# 04B-345.net
KiCad netlist of a schematic drawn in EAGLE
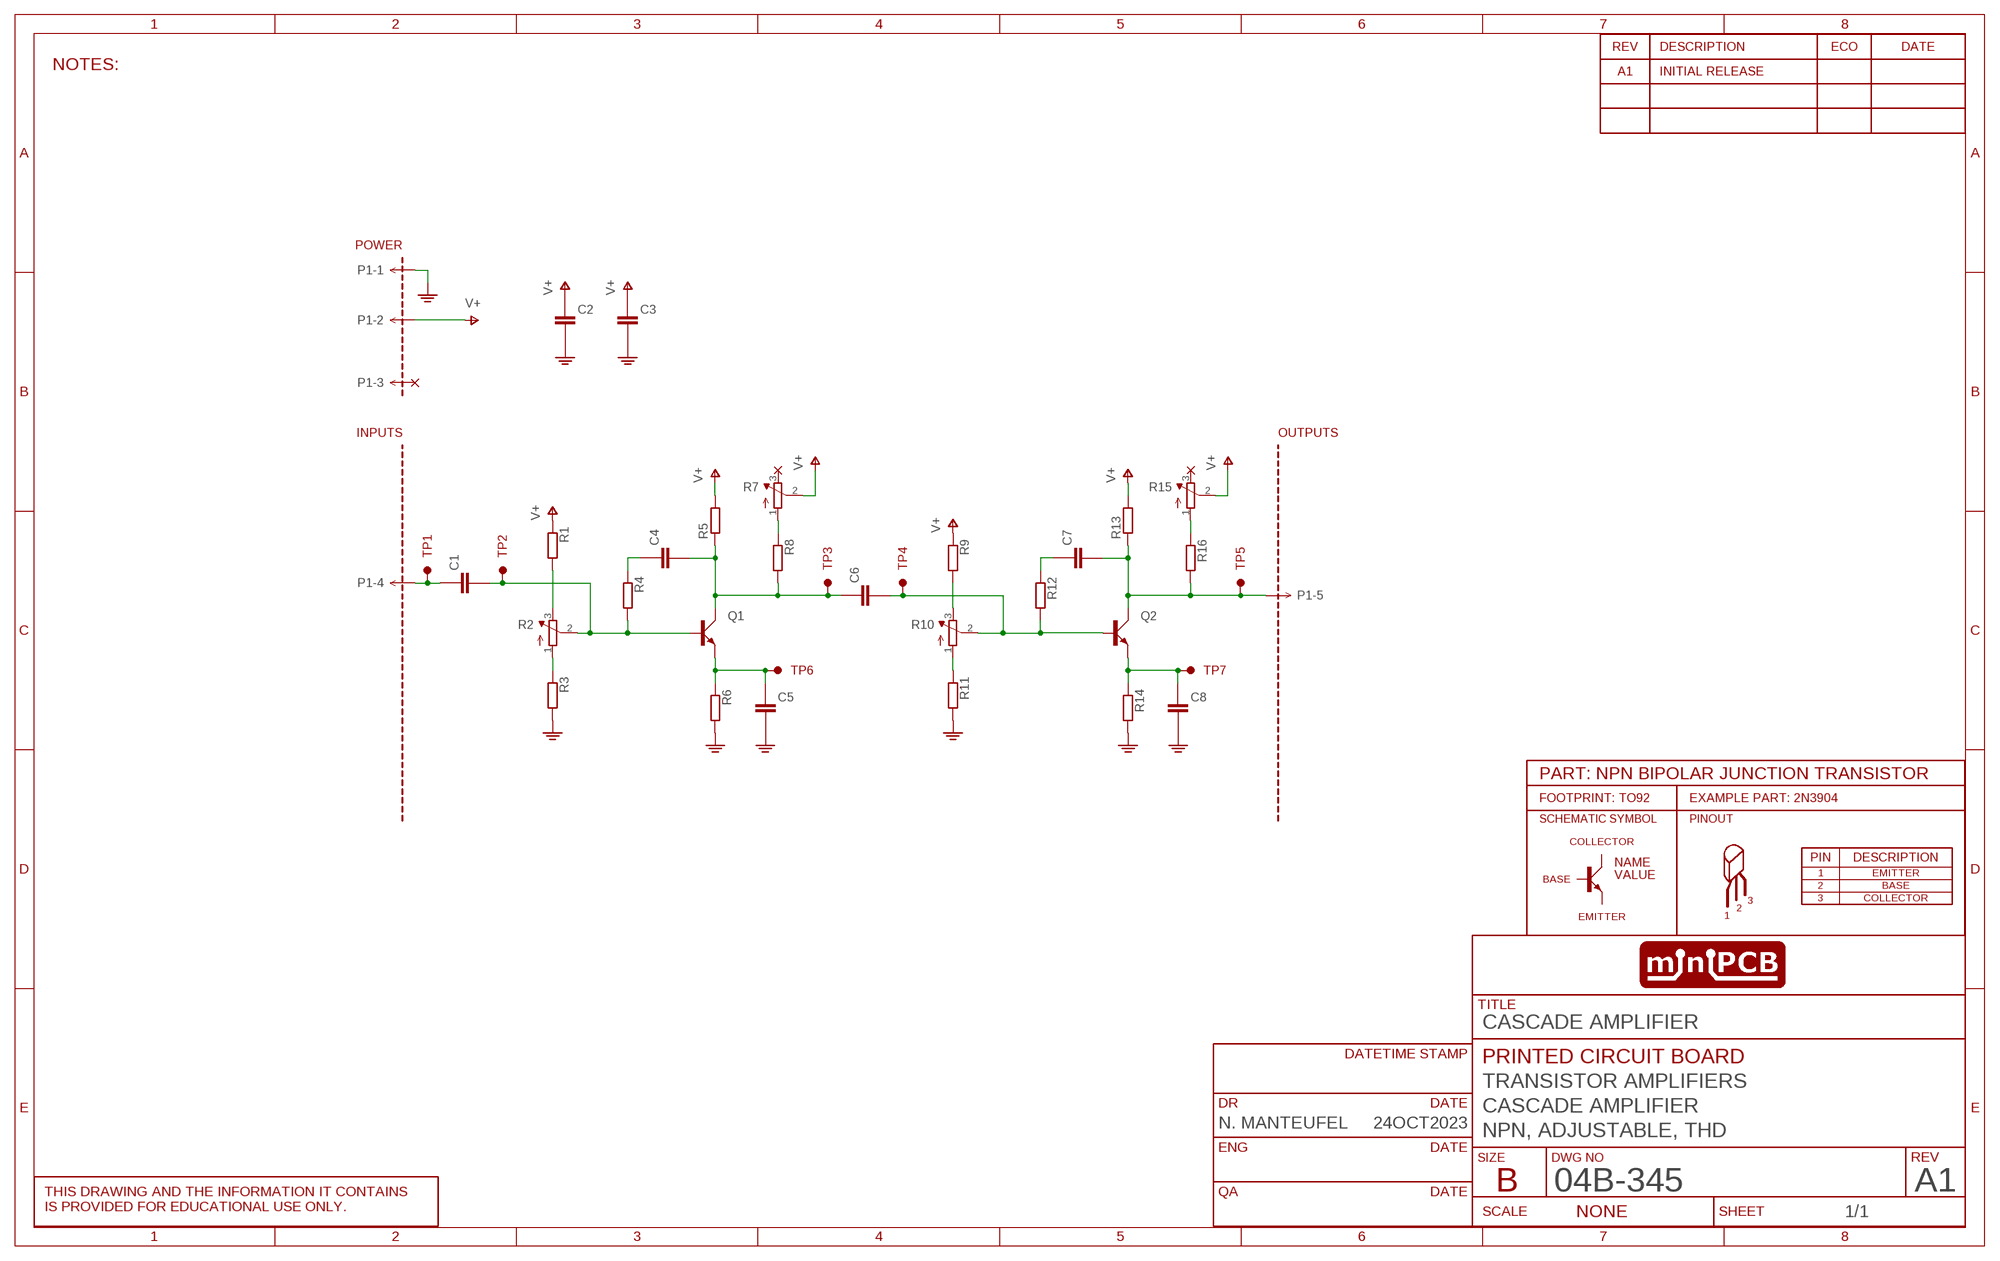
[diagram p0: schematic, sheet 1]

(export (version "E")
  (design (tool "Eeschema 10.0.6"))
  (components
    (comp (ref "C1")
      (value "CAPACITORTHD")
      (footprint "eagle-import:C050-024X044")
      (libsource (lib "eagle-import") (part "CAPACITORTHD"))
    )
    (comp (ref "C2")
      (value "CAPACITORTHD")
      (footprint "eagle-import:C050-024X044")
      (libsource (lib "eagle-import") (part "CAPACITORTHD"))
    )
    (comp (ref "C3")
      (value "CAPACITOR_10")
      (footprint "eagle-import:C5MM")
      (libsource (lib "eagle-import") (part "CAPACITOR_10"))
    )
    (comp (ref "C4")
      (value "CAPACITORTHD")
      (footprint "eagle-import:C050-024X044")
      (libsource (lib "eagle-import") (part "CAPACITORTHD"))
    )
    (comp (ref "C5")
      (value "CAPACITOR_10")
      (footprint "eagle-import:C5MM")
      (libsource (lib "eagle-import") (part "CAPACITOR_10"))
    )
    (comp (ref "C6")
      (value "CAPACITORTHD")
      (footprint "eagle-import:C050-024X044")
      (libsource (lib "eagle-import") (part "CAPACITORTHD"))
    )
    (comp (ref "C7")
      (value "CAPACITORTHD")
      (footprint "eagle-import:C050-024X044")
      (libsource (lib "eagle-import") (part "CAPACITORTHD"))
    )
    (comp (ref "C8")
      (value "CAPACITOR_10")
      (footprint "eagle-import:C5MM")
      (libsource (lib "eagle-import") (part "CAPACITOR_10"))
    )
    (comp (ref "P1")
      (value "MINIPCB_5P5P")
      (footprint "eagle-import:PINS_1X5")
      (libsource (lib "eagle-import") (part "MINIPCB_5P5P"))
    )
    (comp (ref "PCB1")
      (value "MINIPCB_0P50X75")
      (footprint "eagle-import:MINIPCB_0P_50X75")
      (libsource (lib "eagle-import") (part "MINIPCB_0P50X75"))
    )
    (comp (ref "Q1")
      (value "BJT_NPNEBC")
      (footprint "eagle-import:TO92-EBC-OVAL")
      (libsource (lib "eagle-import") (part "BJT_NPNEBC"))
    )
    (comp (ref "Q2")
      (value "BJT_NPNEBC")
      (footprint "eagle-import:TO92-EBC-OVAL")
      (libsource (lib "eagle-import") (part "BJT_NPNEBC"))
    )
    (comp (ref "R1")
      (value "RESISTORTHD")
      (footprint "eagle-import:0204_10")
      (libsource (lib "eagle-import") (part "RESISTORTHD"))
    )
    (comp (ref "R2")
      (value "TRIMPOT0.100THD")
      (footprint "eagle-import:TRIM_0100")
      (libsource (lib "eagle-import") (part "TRIMPOT0.100THD"))
    )
    (comp (ref "R3")
      (value "RESISTORTHD")
      (footprint "eagle-import:0204_10")
      (libsource (lib "eagle-import") (part "RESISTORTHD"))
    )
    (comp (ref "R4")
      (value "RESISTORTHD")
      (footprint "eagle-import:0204_10")
      (libsource (lib "eagle-import") (part "RESISTORTHD"))
    )
    (comp (ref "R5")
      (value "RESISTORTHD")
      (footprint "eagle-import:0204_10")
      (libsource (lib "eagle-import") (part "RESISTORTHD"))
    )
    (comp (ref "R6")
      (value "RESISTORTHD")
      (footprint "eagle-import:0204_10")
      (libsource (lib "eagle-import") (part "RESISTORTHD"))
    )
    (comp (ref "R7")
      (value "TRIMPOT0.100THD")
      (footprint "eagle-import:TRIM_0100")
      (libsource (lib "eagle-import") (part "TRIMPOT0.100THD"))
    )
    (comp (ref "R8")
      (value "RESISTORTHD")
      (footprint "eagle-import:0204_10")
      (libsource (lib "eagle-import") (part "RESISTORTHD"))
    )
    (comp (ref "R9")
      (value "RESISTORTHD")
      (footprint "eagle-import:0204_10")
      (libsource (lib "eagle-import") (part "RESISTORTHD"))
    )
    (comp (ref "R10")
      (value "TRIMPOT0.100THD")
      (footprint "eagle-import:TRIM_0100")
      (libsource (lib "eagle-import") (part "TRIMPOT0.100THD"))
    )
    (comp (ref "R11")
      (value "RESISTORTHD")
      (footprint "eagle-import:0204_10")
      (libsource (lib "eagle-import") (part "RESISTORTHD"))
    )
    (comp (ref "R12")
      (value "RESISTORTHD")
      (footprint "eagle-import:0204_10")
      (libsource (lib "eagle-import") (part "RESISTORTHD"))
    )
    (comp (ref "R13")
      (value "RESISTORTHD")
      (footprint "eagle-import:0204_10")
      (libsource (lib "eagle-import") (part "RESISTORTHD"))
    )
    (comp (ref "R14")
      (value "RESISTORTHD")
      (footprint "eagle-import:0204_10")
      (libsource (lib "eagle-import") (part "RESISTORTHD"))
    )
    (comp (ref "R15")
      (value "TRIMPOT0.100THD")
      (footprint "eagle-import:TRIM_0100")
      (libsource (lib "eagle-import") (part "TRIMPOT0.100THD"))
    )
    (comp (ref "R16")
      (value "RESISTORTHD")
      (footprint "eagle-import:0204_10")
      (libsource (lib "eagle-import") (part "RESISTORTHD"))
    )
    (comp (ref "TP1")
      (value "TESTPOINTKE5000-SMTEXT")
      (footprint "eagle-import:PINS_1_TESTPOINT_KE5000_NOTEXT")
      (libsource (lib "eagle-import") (part "TESTPOINTKE5000-SMTEXT"))
    )
    (comp (ref "TP2")
      (value "TESTPOINTKE5000-SMTEXT")
      (footprint "eagle-import:PINS_1_TESTPOINT_KE5000_NOTEXT")
      (libsource (lib "eagle-import") (part "TESTPOINTKE5000-SMTEXT"))
    )
    (comp (ref "TP3")
      (value "TESTPOINTKE5000-SMTEXT")
      (footprint "eagle-import:PINS_1_TESTPOINT_KE5000_NOTEXT")
      (libsource (lib "eagle-import") (part "TESTPOINTKE5000-SMTEXT"))
    )
    (comp (ref "TP4")
      (value "TESTPOINTKE5000-SMTEXT")
      (footprint "eagle-import:PINS_1_TESTPOINT_KE5000_NOTEXT")
      (libsource (lib "eagle-import") (part "TESTPOINTKE5000-SMTEXT"))
    )
    (comp (ref "TP5")
      (value "TESTPOINTKE5000-SMTEXT")
      (footprint "eagle-import:PINS_1_TESTPOINT_KE5000_NOTEXT")
      (libsource (lib "eagle-import") (part "TESTPOINTKE5000-SMTEXT"))
    )
    (comp (ref "TP6")
      (value "TESTPOINTKE5000-SMTEXT")
      (footprint "eagle-import:PINS_1_TESTPOINT_KE5000_NOTEXT")
      (libsource (lib "eagle-import") (part "TESTPOINTKE5000-SMTEXT"))
    )
    (comp (ref "TP7")
      (value "TESTPOINTKE5000-SMTEXT")
      (footprint "eagle-import:PINS_1_TESTPOINT_KE5000_NOTEXT")
      (libsource (lib "eagle-import") (part "TESTPOINTKE5000-SMTEXT"))
    )
  )
  (nets
    (net (code "1") (name "GND") (class "Default")
      (node (ref "C2") (pin "2") (pinfunction "-_2") (pintype "passive"))
      (node (ref "C3") (pin "-") (pinfunction "-_-") (pintype "passive"))
      (node (ref "C5") (pin "-") (pinfunction "-_-") (pintype "passive"))
      (node (ref "C8") (pin "-") (pinfunction "-_-") (pintype "passive"))
      (node (ref "P1") (pin "1") (pinfunction "1_1") (pintype "bidirectional"))
      (node (ref "R11") (pin "2") (pinfunction "2_2") (pintype "passive"))
      (node (ref "R14") (pin "2") (pinfunction "2_2") (pintype "passive"))
      (node (ref "R3") (pin "2") (pinfunction "2_2") (pintype "passive"))
      (node (ref "R6") (pin "2") (pinfunction "2_2") (pintype "passive"))
    )
    (net (code "2") (name "Net-(C1-+)") (class "Default")
      (node (ref "C1") (pin "1") (pinfunction "+_1") (pintype "passive"))
      (node (ref "P1") (pin "4") (pinfunction "1_4") (pintype "bidirectional"))
      (node (ref "TP1") (pin "1") (pinfunction "1_1") (pintype "bidirectional"))
    )
    (net (code "3") (name "Net-(C1--)") (class "Default")
      (node (ref "C1") (pin "2") (pinfunction "-_2") (pintype "passive"))
      (node (ref "Q1") (pin "B") (pinfunction "B_B") (pintype "passive"))
      (node (ref "R2") (pin "2") (pinfunction "S_2") (pintype "passive"))
      (node (ref "R4") (pin "2") (pinfunction "2_2") (pintype "passive"))
      (node (ref "TP2") (pin "1") (pinfunction "1_1") (pintype "bidirectional"))
    )
    (net (code "4") (name "Net-(C4-+)") (class "Default")
      (node (ref "C4") (pin "1") (pinfunction "+_1") (pintype "passive"))
      (node (ref "R4") (pin "1") (pinfunction "1_1") (pintype "passive"))
    )
    (net (code "5") (name "Net-(C4--)") (class "Default")
      (node (ref "C4") (pin "2") (pinfunction "-_2") (pintype "passive"))
      (node (ref "C6") (pin "1") (pinfunction "+_1") (pintype "passive"))
      (node (ref "Q1") (pin "C") (pinfunction "C_C") (pintype "passive"))
      (node (ref "R5") (pin "1") (pinfunction "1_1") (pintype "passive"))
      (node (ref "R8") (pin "2") (pinfunction "2_2") (pintype "passive"))
      (node (ref "TP3") (pin "1") (pinfunction "1_1") (pintype "bidirectional"))
    )
    (net (code "6") (name "Net-(C5-Pad+)") (class "Default")
      (node (ref "C5") (pin "+") (pinfunction "+_+") (pintype "passive"))
      (node (ref "Q1") (pin "E") (pinfunction "E_E") (pintype "passive"))
      (node (ref "R6") (pin "1") (pinfunction "1_1") (pintype "passive"))
      (node (ref "TP6") (pin "1") (pinfunction "1_1") (pintype "bidirectional"))
    )
    (net (code "7") (name "Net-(C6--)") (class "Default")
      (node (ref "C6") (pin "2") (pinfunction "-_2") (pintype "passive"))
      (node (ref "Q2") (pin "B") (pinfunction "B_B") (pintype "passive"))
      (node (ref "R10") (pin "2") (pinfunction "S_2") (pintype "passive"))
      (node (ref "R12") (pin "2") (pinfunction "2_2") (pintype "passive"))
      (node (ref "TP4") (pin "1") (pinfunction "1_1") (pintype "bidirectional"))
    )
    (net (code "8") (name "Net-(C7-+)") (class "Default")
      (node (ref "C7") (pin "1") (pinfunction "+_1") (pintype "passive"))
      (node (ref "R12") (pin "1") (pinfunction "1_1") (pintype "passive"))
    )
    (net (code "9") (name "Net-(C7--)") (class "Default")
      (node (ref "C7") (pin "2") (pinfunction "-_2") (pintype "passive"))
      (node (ref "P1") (pin "5") (pinfunction "1_5") (pintype "bidirectional"))
      (node (ref "Q2") (pin "C") (pinfunction "C_C") (pintype "passive"))
      (node (ref "R13") (pin "1") (pinfunction "1_1") (pintype "passive"))
      (node (ref "R16") (pin "2") (pinfunction "2_2") (pintype "passive"))
      (node (ref "TP5") (pin "1") (pinfunction "1_1") (pintype "bidirectional"))
    )
    (net (code "10") (name "Net-(C8-Pad+)") (class "Default")
      (node (ref "C8") (pin "+") (pinfunction "+_+") (pintype "passive"))
      (node (ref "Q2") (pin "E") (pinfunction "E_E") (pintype "passive"))
      (node (ref "R14") (pin "1") (pinfunction "1_1") (pintype "passive"))
      (node (ref "TP7") (pin "1") (pinfunction "1_1") (pintype "bidirectional"))
    )
    (net (code "11") (name "Net-(R2-A)") (class "Default")
      (node (ref "R2") (pin "1") (pinfunction "A_1") (pintype "passive"))
      (node (ref "R3") (pin "1") (pinfunction "1_1") (pintype "passive"))
    )
    (net (code "12") (name "Net-(R2-E)") (class "Default")
      (node (ref "R1") (pin "2") (pinfunction "2_2") (pintype "passive"))
      (node (ref "R2") (pin "3") (pinfunction "E_3") (pintype "passive"))
    )
    (net (code "13") (name "Net-(R7-A)") (class "Default")
      (node (ref "R7") (pin "1") (pinfunction "A_1") (pintype "passive"))
      (node (ref "R8") (pin "1") (pinfunction "1_1") (pintype "passive"))
    )
    (net (code "14") (name "Net-(R10-A)") (class "Default")
      (node (ref "R10") (pin "1") (pinfunction "A_1") (pintype "passive"))
      (node (ref "R11") (pin "1") (pinfunction "1_1") (pintype "passive"))
    )
    (net (code "15") (name "Net-(R10-E)") (class "Default")
      (node (ref "R10") (pin "3") (pinfunction "E_3") (pintype "passive"))
      (node (ref "R9") (pin "2") (pinfunction "2_2") (pintype "passive"))
    )
    (net (code "16") (name "Net-(R15-A)") (class "Default")
      (node (ref "R15") (pin "1") (pinfunction "A_1") (pintype "passive"))
      (node (ref "R16") (pin "1") (pinfunction "1_1") (pintype "passive"))
    )
    (net (code "17") (name "V+") (class "Default")
      (node (ref "C2") (pin "1") (pinfunction "+_1") (pintype "passive"))
      (node (ref "C3") (pin "+") (pinfunction "+_+") (pintype "passive"))
      (node (ref "P1") (pin "2") (pinfunction "1_2") (pintype "bidirectional"))
      (node (ref "R1") (pin "1") (pinfunction "1_1") (pintype "passive"))
      (node (ref "R13") (pin "2") (pinfunction "2_2") (pintype "passive"))
      (node (ref "R15") (pin "2") (pinfunction "S_2") (pintype "passive"))
      (node (ref "R5") (pin "2") (pinfunction "2_2") (pintype "passive"))
      (node (ref "R7") (pin "2") (pinfunction "S_2") (pintype "passive"))
      (node (ref "R9") (pin "1") (pinfunction "1_1") (pintype "passive"))
    )
    (net (code "18") (name "unconnected-(P1C-1-Pad3)") (class "Default")
      (node (ref "P1") (pin "3") (pinfunction "1_3") (pintype "bidirectional"))
    )
    (net (code "19") (name "unconnected-(R7-E-Pad3)") (class "Default")
      (node (ref "R7") (pin "3") (pinfunction "E_3") (pintype "passive"))
    )
    (net (code "20") (name "unconnected-(R15-E-Pad3)") (class "Default")
      (node (ref "R15") (pin "3") (pinfunction "E_3") (pintype "passive"))
    )
  )
)
